# CHANNEL.net
KiCad netlist of a schematic drawn in Altium Designer
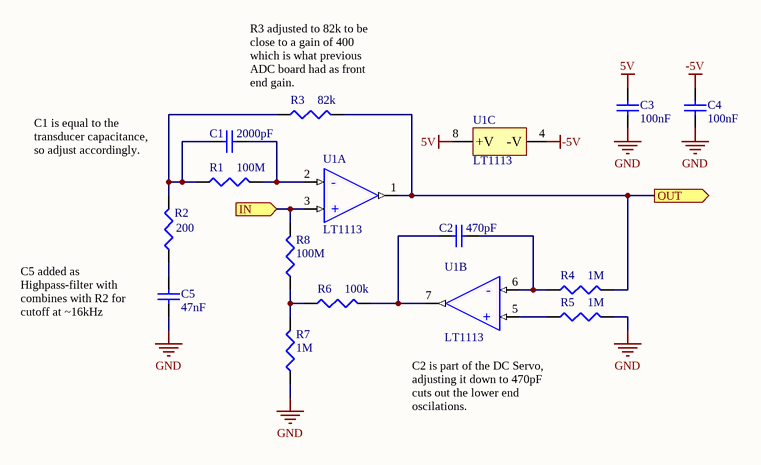
[diagram p0: CHANNEL.SchDoc]

(export (version "E")
  (design (tool "Eeschema 10.0.6"))
  (components
    (comp (ref "C1")
      (value "2000pF")
      (footprint "1608[0603]")
      (description "Capacitor (Semiconductor SIM Model)")
      (fields (field (name "Comment") "Cap Semi") (field (name "PUBLISHER") "Altium Limited"))
      (libsource (lib "Miscellaneous Devices") (part "Cap Semi"))
    )
    (comp (ref "C2")
      (value "470pF")
      (footprint "1608[0603]")
      (description "Capacitor (Semiconductor SIM Model)")
      (fields (field (name "Comment") "Cap Semi") (field (name "PUBLISHER") "Altium Limited"))
      (libsource (lib "Miscellaneous Devices") (part "Cap Semi"))
    )
    (comp (ref "C3")
      (value "100nF")
      (footprint "1608[0603]")
      (description "Capacitor (Semiconductor SIM Model)")
      (fields (field (name "Comment") "Cap Semi") (field (name "PUBLISHER") "Altium Limited"))
      (libsource (lib "Miscellaneous Devices") (part "Cap Semi"))
    )
    (comp (ref "C4")
      (value "100nF")
      (footprint "1608[0603]")
      (description "Capacitor (Semiconductor SIM Model)")
      (fields (field (name "Comment") "Cap Semi") (field (name "PUBLISHER") "Altium Limited"))
      (libsource (lib "Miscellaneous Devices") (part "Cap Semi"))
    )
    (comp (ref "C5")
      (value "47nF")
      (footprint "1608[0603]")
      (description "Capacitor (Semiconductor SIM Model)")
      (fields (field (name "Comment") "Cap Semi") (field (name "PUBLISHER") "Altium Limited"))
      (libsource (lib "Miscellaneous Devices") (part "Cap Semi"))
    )
    (comp (ref "R1")
      (value "100M")
      (footprint "J1-0603")
      (description "Resistor")
      (fields (field (name "Comment") "Res3") (field (name "PUBLISHER") "Altium Limited"))
      (libsource (lib "Miscellaneous Devices") (part "Res3"))
    )
    (comp (ref "R2")
      (value "200")
      (footprint "J1-0603")
      (description "Resistor")
      (fields (field (name "Comment") "Res3") (field (name "PUBLISHER") "Altium Limited"))
      (libsource (lib "Miscellaneous Devices") (part "Res3"))
    )
    (comp (ref "R3")
      (value "82k")
      (footprint "J1-0603")
      (description "Resistor")
      (fields (field (name "Comment") "Res3") (field (name "PUBLISHER") "Altium Limited"))
      (libsource (lib "Miscellaneous Devices") (part "Res3"))
    )
    (comp (ref "R4")
      (value "1M")
      (footprint "J1-0603")
      (description "Resistor")
      (fields (field (name "Comment") "Res3") (field (name "PUBLISHER") "Altium Limited"))
      (libsource (lib "Miscellaneous Devices") (part "Res3"))
    )
    (comp (ref "R5")
      (value "1M")
      (footprint "J1-0603")
      (description "Resistor")
      (fields (field (name "Comment") "Res3") (field (name "PUBLISHER") "Altium Limited"))
      (libsource (lib "Miscellaneous Devices") (part "Res3"))
    )
    (comp (ref "R6")
      (value "100k")
      (footprint "J1-0603")
      (description "Resistor")
      (fields (field (name "Comment") "Res3") (field (name "PUBLISHER") "Altium Limited"))
      (libsource (lib "Miscellaneous Devices") (part "Res3"))
    )
    (comp (ref "R7")
      (value "1M")
      (footprint "J1-0603")
      (description "Resistor")
      (fields (field (name "Comment") "Res3") (field (name "PUBLISHER") "Altium Limited"))
      (libsource (lib "Miscellaneous Devices") (part "Res3"))
    )
    (comp (ref "R8")
      (value "100M")
      (footprint "J1-0603")
      (description "Resistor")
      (fields (field (name "Comment") "Res3") (field (name "PUBLISHER") "Altium Limited"))
      (libsource (lib "Miscellaneous Devices") (part "Res3"))
    )
    (comp (ref "U1")
      (value "LT1113")
      (footprint "SO8_L")
      (description "LT1113 Opamp")
      (libsource (lib "") (part "LT1113_2"))
    )
  )
  (nets
    (net (code "1") (name "-5V") (class "Default")
      (node (ref "C4") (pin "2") (pinfunction "2_2") (pintype "passive"))
      (node (ref "U1") (pin "4") (pinfunction "-V_4") (pintype "power_in"))
    )
    (net (code "2") (name "/IN") (class "Default")
      (node (ref "R8") (pin "2") (pinfunction "2_2") (pintype "passive"))
      (node (ref "U1") (pin "3") (pinfunction "+_3") (pintype "input"))
    )
    (net (code "3") (name "/OUT") (class "Default")
      (node (ref "R3") (pin "2") (pinfunction "2_2") (pintype "passive"))
      (node (ref "R4") (pin "2") (pinfunction "2_2") (pintype "passive"))
      (node (ref "U1") (pin "1") (pinfunction "OUTA_1") (pintype "output"))
    )
    (net (code "4") (name "5V") (class "Default")
      (node (ref "C3") (pin "2") (pinfunction "2_2") (pintype "passive"))
      (node (ref "U1") (pin "8") (pinfunction "+V_8") (pintype "power_in"))
    )
    (net (code "5") (name "GND") (class "Default")
      (node (ref "C3") (pin "1") (pinfunction "1_1") (pintype "passive"))
      (node (ref "C4") (pin "1") (pinfunction "1_1") (pintype "passive"))
      (node (ref "C5") (pin "1") (pinfunction "1_1") (pintype "passive"))
      (node (ref "R5") (pin "2") (pinfunction "2_2") (pintype "passive"))
      (node (ref "R7") (pin "1") (pinfunction "1_1") (pintype "passive"))
    )
    (net (code "6") (name "Net-(C1-Pad1)") (class "Default")
      (node (ref "C1") (pin "1") (pinfunction "1_1") (pintype "passive"))
      (node (ref "R1") (pin "1") (pinfunction "1_1") (pintype "passive"))
      (node (ref "R2") (pin "2") (pinfunction "2_2") (pintype "passive"))
      (node (ref "R3") (pin "1") (pinfunction "1_1") (pintype "passive"))
    )
    (net (code "7") (name "Net-(C5-Pad2)") (class "Default")
      (node (ref "C5") (pin "2") (pinfunction "2_2") (pintype "passive"))
      (node (ref "R2") (pin "1") (pinfunction "1_1") (pintype "passive"))
    )
    (net (code "8") (name "Net-(R6-Pad1)") (class "Default")
      (node (ref "R6") (pin "1") (pinfunction "1_1") (pintype "passive"))
      (node (ref "R7") (pin "2") (pinfunction "2_2") (pintype "passive"))
      (node (ref "R8") (pin "1") (pinfunction "1_1") (pintype "passive"))
    )
    (net (code "9") (name "Net-(U1A--)") (class "Default")
      (node (ref "C1") (pin "2") (pinfunction "2_2") (pintype "passive"))
      (node (ref "R1") (pin "2") (pinfunction "2_2") (pintype "passive"))
      (node (ref "U1") (pin "2") (pinfunction "-_2") (pintype "input"))
    )
    (net (code "10") (name "Net-(U1B-+)") (class "Default")
      (node (ref "R5") (pin "1") (pinfunction "1_1") (pintype "passive"))
      (node (ref "U1") (pin "5") (pinfunction "+_5") (pintype "input"))
    )
    (net (code "11") (name "Net-(U1B--)") (class "Default")
      (node (ref "C2") (pin "2") (pinfunction "2_2") (pintype "passive"))
      (node (ref "R4") (pin "1") (pinfunction "1_1") (pintype "passive"))
      (node (ref "U1") (pin "6") (pinfunction "-_6") (pintype "input"))
    )
    (net (code "12") (name "Net-(U1B-OUTA)") (class "Default")
      (node (ref "C2") (pin "1") (pinfunction "1_1") (pintype "passive"))
      (node (ref "R6") (pin "2") (pinfunction "2_2") (pintype "passive"))
      (node (ref "U1") (pin "7") (pinfunction "OUTA_7") (pintype "output"))
    )
  )
)
